# Microcontroller.net
KiCad netlist of a schematic drawn in Altium Designer
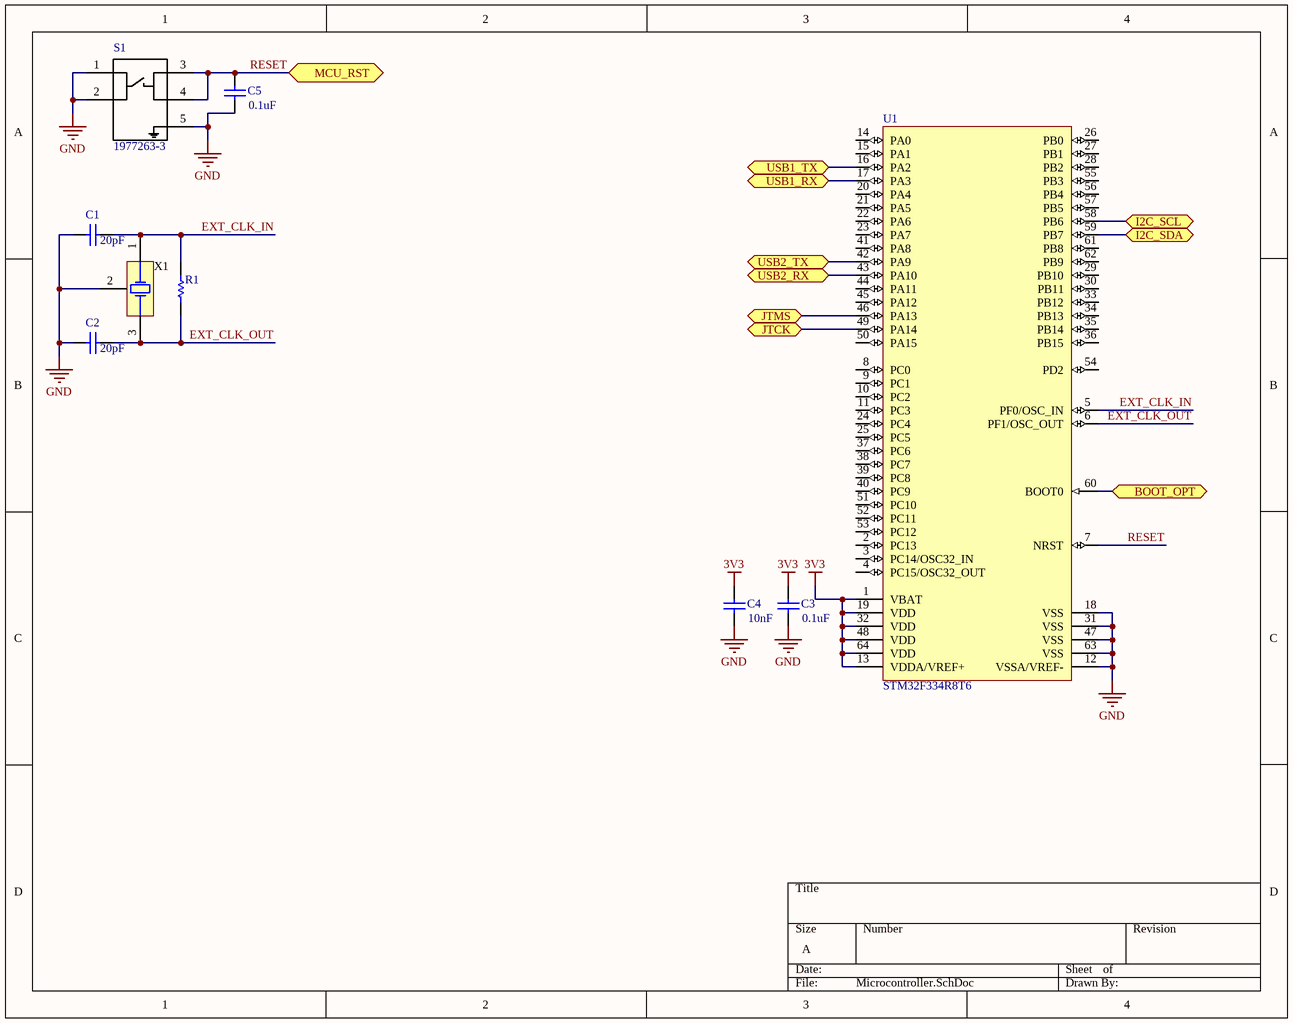
[diagram p0: Microcontroller.SchDoc]

(export (version "E")
  (design (tool "Eeschema 10.0.6"))
  (components
    (comp (ref "C1")
      (value "20pF")
      (footprint "CAPC1206(3216)100_M")
      (description "CAP 20pF 100V ±10% 1206 (3216 Metric) Thickness 1mm SMD")
      (fields (field (name "TOLERANCE") "Â±10%") (field (name "Comment") "CAP 20pF 100V 1206(3216)"))
      (libsource (lib "Altium Content Vault") (part "CAP"))
    )
    (comp (ref "C2")
      (value "20pF")
      (footprint "CAPC1206(3216)100_M")
      (description "CAP 20pF 100V ±10% 1206 (3216 Metric) Thickness 1mm SMD")
      (fields (field (name "TOLERANCE") "Â±10%") (field (name "Comment") "CAP 20pF 100V 1206(3216)"))
      (libsource (lib "Altium Content Vault") (part "CAP"))
    )
    (comp (ref "C3")
      (value "0.1uF")
      (footprint "CAPC3216X100X50LL20T25")
      (description "CAP CER 0.1UF 25V 10% X7R 1206")
      (fields (field (name "PARTNUMBER") "C1206F104K3RACTU"))
      (libsource (lib "Altium Content Vault") (part "CAP-NP-2"))
    )
    (comp (ref "C4")
      (value "C1206C103K1RAC")
      (footprint "CAPC3216X88X50LL20T25")
      (description "Chip Capacitor, 0.01 uF, +/- 10%, 100 V, -55 to 125 degC, 1206 (3216 Metric), RoHS, Tape and Reel")
      (fields (field (name "CAPACITANCE") "10nF") (field (name "MANUFACTURER") "Kemet"))
      (libsource (lib "") (part "CAP-NP-2_1"))
    )
    (comp (ref "C5")
      (value "0.1uF")
      (footprint "CAPC3216X100X50LL20T25")
      (description "CAP CER 0.1UF 25V 10% X7R 1206")
      (fields (field (name "PARTNUMBER") "C1206F104K3RACTU"))
      (libsource (lib "Altium Content Vault") (part "CAP-NP-2"))
    )
    (comp (ref "R1")
      (value "1M8 5% 1206(3216)")
      (footprint "RESC1206(3216)_M")
      (description "1M8 0.25W 5% 1206 (3216 Metric)  SMD")
      (fields (field (name "TOLERANCE") "5 %") (field (name "POWER") "0.25 W"))
      (libsource (lib "Altium Content Vault") (part "RES"))
    )
    (comp (ref "S1")
      (value "1977263-3")
      (footprint "SW_1977263-3")
      (description "Switch Tactile OFF _ON_ SPST Round Button Gull Wing 0.05A 24VDC 1000000Cycle 2.55N SMD Bulk")
      (fields (field (name "MF") "TE Connectivity / AMP"))
      (libsource (lib "HRTAltiumLib") (part "1977263-3"))
    )
    (comp (ref "U1")
      (value "STM32F334R8T6")
      (footprint "STM-LQFP64_L")
      (libsource (lib "Altium Content Vault") (part "MC-ARM-STM32F334-LQFP64"))
    )
    (comp (ref "X1")
      (value "ECS-200-20-4X-3IL")
      (footprint "ECS-4X-3IL")
      (description "Quartz Crystal, 20 MHz, 20 pF, -10 to 70 degC, 2-Pin THD, RoHS, Bulk")
      (fields (field (name "MANUFACTURER") "ECS"))
      (libsource (lib "Altium Content Vault") (part "XTAL-1-3-3"))
    )
  )
  (nets
    (net (code "1") (name "/BOOT_OPT") (class "Default")
      (node (ref "U1") (pin "60") (pinfunction "BOOT0_60") (pintype "input"))
    )
    (net (code "2") (name "/EXT_CLK_IN") (class "Default")
      (node (ref "C1") (pin "2") (pinfunction "2_2") (pintype "passive"))
      (node (ref "R1") (pin "2") (pinfunction "2_2") (pintype "passive"))
      (node (ref "U1") (pin "5") (pinfunction "PF0/OSC_IN_5") (pintype "bidirectional"))
      (node (ref "X1") (pin "1") (pinfunction "1_1") (pintype "passive"))
    )
    (net (code "3") (name "/EXT_CLK_OUT") (class "Default")
      (node (ref "C2") (pin "2") (pinfunction "2_2") (pintype "passive"))
      (node (ref "R1") (pin "1") (pinfunction "1_1") (pintype "passive"))
      (node (ref "U1") (pin "6") (pinfunction "PF1/OSC_OUT_6") (pintype "bidirectional"))
      (node (ref "X1") (pin "3") (pinfunction "3_3") (pintype "passive"))
    )
    (net (code "4") (name "/I2C_SCL") (class "Default")
      (node (ref "U1") (pin "58") (pinfunction "PB6_58") (pintype "bidirectional"))
    )
    (net (code "5") (name "/I2C_SDA") (class "Default")
      (node (ref "U1") (pin "59") (pinfunction "PB7_59") (pintype "bidirectional"))
    )
    (net (code "6") (name "/JTCK") (class "Default")
      (node (ref "U1") (pin "49") (pinfunction "PA14_49") (pintype "bidirectional"))
    )
    (net (code "7") (name "/JTMS") (class "Default")
      (node (ref "U1") (pin "46") (pinfunction "PA13_46") (pintype "bidirectional"))
    )
    (net (code "8") (name "/RESET") (class "Default")
      (node (ref "C5") (pin "1") (pinfunction "1_1") (pintype "passive"))
      (node (ref "S1") (pin "3") (pinfunction "3_3") (pintype "passive"))
      (node (ref "S1") (pin "4") (pinfunction "4_4") (pintype "passive"))
      (node (ref "U1") (pin "7") (pinfunction "NRST_7") (pintype "bidirectional"))
    )
    (net (code "9") (name "/USB1_RX") (class "Default")
      (node (ref "U1") (pin "17") (pinfunction "PA3_17") (pintype "bidirectional"))
    )
    (net (code "10") (name "/USB1_TX") (class "Default")
      (node (ref "U1") (pin "16") (pinfunction "PA2_16") (pintype "bidirectional"))
    )
    (net (code "11") (name "/USB2_RX") (class "Default")
      (node (ref "U1") (pin "43") (pinfunction "PA10_43") (pintype "bidirectional"))
    )
    (net (code "12") (name "/USB2_TX") (class "Default")
      (node (ref "U1") (pin "42") (pinfunction "PA9_42") (pintype "bidirectional"))
    )
    (net (code "13") (name "3V3") (class "Default")
      (node (ref "C3") (pin "1") (pinfunction "1_1") (pintype "passive"))
      (node (ref "C4") (pin "2") (pinfunction "2_2") (pintype "passive"))
      (node (ref "U1") (pin "1") (pinfunction "VBAT_1") (pintype "power_in"))
      (node (ref "U1") (pin "13") (pinfunction "VDDA/VREF+_13") (pintype "power_in"))
      (node (ref "U1") (pin "19") (pinfunction "VDD_19") (pintype "power_in"))
      (node (ref "U1") (pin "32") (pinfunction "VDD_32") (pintype "power_in"))
      (node (ref "U1") (pin "48") (pinfunction "VDD_48") (pintype "power_in"))
      (node (ref "U1") (pin "64") (pinfunction "VDD_64") (pintype "power_in"))
    )
    (net (code "14") (name "GND") (class "Default")
      (node (ref "C1") (pin "1") (pinfunction "1_1") (pintype "passive"))
      (node (ref "C2") (pin "1") (pinfunction "1_1") (pintype "passive"))
      (node (ref "C3") (pin "2") (pinfunction "2_2") (pintype "passive"))
      (node (ref "C4") (pin "1") (pinfunction "1_1") (pintype "passive"))
      (node (ref "C5") (pin "2") (pinfunction "2_2") (pintype "passive"))
      (node (ref "S1") (pin "1") (pinfunction "1_1") (pintype "passive"))
      (node (ref "S1") (pin "2") (pinfunction "2_2") (pintype "passive"))
      (node (ref "S1") (pin "5") (pinfunction "GND_5") (pintype "power_in"))
      (node (ref "U1") (pin "12") (pinfunction "VSSA/VREF-_12") (pintype "power_in"))
      (node (ref "U1") (pin "18") (pinfunction "VSS_18") (pintype "power_in"))
      (node (ref "U1") (pin "31") (pinfunction "VSS_31") (pintype "power_in"))
      (node (ref "U1") (pin "47") (pinfunction "VSS_47") (pintype "power_in"))
      (node (ref "U1") (pin "63") (pinfunction "VSS_63") (pintype "power_in"))
      (node (ref "X1") (pin "2") (pinfunction "2_2") (pintype "passive"))
    )
    (net (code "15") (name "unconnected-(U1-PA0-Pad14)") (class "Default")
      (node (ref "U1") (pin "14") (pinfunction "PA0_14") (pintype "bidirectional"))
    )
    (net (code "16") (name "unconnected-(U1-PA1-Pad15)") (class "Default")
      (node (ref "U1") (pin "15") (pinfunction "PA1_15") (pintype "bidirectional"))
    )
    (net (code "17") (name "unconnected-(U1-PA4-Pad20)") (class "Default")
      (node (ref "U1") (pin "20") (pinfunction "PA4_20") (pintype "bidirectional"))
    )
    (net (code "18") (name "unconnected-(U1-PA5-Pad21)") (class "Default")
      (node (ref "U1") (pin "21") (pinfunction "PA5_21") (pintype "bidirectional"))
    )
    (net (code "19") (name "unconnected-(U1-PA6-Pad22)") (class "Default")
      (node (ref "U1") (pin "22") (pinfunction "PA6_22") (pintype "bidirectional"))
    )
    (net (code "20") (name "unconnected-(U1-PA7-Pad23)") (class "Default")
      (node (ref "U1") (pin "23") (pinfunction "PA7_23") (pintype "bidirectional"))
    )
    (net (code "21") (name "unconnected-(U1-PA8-Pad41)") (class "Default")
      (node (ref "U1") (pin "41") (pinfunction "PA8_41") (pintype "bidirectional"))
    )
    (net (code "22") (name "unconnected-(U1-PA11-Pad44)") (class "Default")
      (node (ref "U1") (pin "44") (pinfunction "PA11_44") (pintype "bidirectional"))
    )
    (net (code "23") (name "unconnected-(U1-PA12-Pad45)") (class "Default")
      (node (ref "U1") (pin "45") (pinfunction "PA12_45") (pintype "bidirectional"))
    )
    (net (code "24") (name "unconnected-(U1-PA15-Pad50)") (class "Default")
      (node (ref "U1") (pin "50") (pinfunction "PA15_50") (pintype "bidirectional"))
    )
    (net (code "25") (name "unconnected-(U1-PB0-Pad26)") (class "Default")
      (node (ref "U1") (pin "26") (pinfunction "PB0_26") (pintype "bidirectional"))
    )
    (net (code "26") (name "unconnected-(U1-PB1-Pad27)") (class "Default")
      (node (ref "U1") (pin "27") (pinfunction "PB1_27") (pintype "bidirectional"))
    )
    (net (code "27") (name "unconnected-(U1-PB2-Pad28)") (class "Default")
      (node (ref "U1") (pin "28") (pinfunction "PB2_28") (pintype "bidirectional"))
    )
    (net (code "28") (name "unconnected-(U1-PB3-Pad55)") (class "Default")
      (node (ref "U1") (pin "55") (pinfunction "PB3_55") (pintype "bidirectional"))
    )
    (net (code "29") (name "unconnected-(U1-PB4-Pad56)") (class "Default")
      (node (ref "U1") (pin "56") (pinfunction "PB4_56") (pintype "bidirectional"))
    )
    (net (code "30") (name "unconnected-(U1-PB5-Pad57)") (class "Default")
      (node (ref "U1") (pin "57") (pinfunction "PB5_57") (pintype "bidirectional"))
    )
    (net (code "31") (name "unconnected-(U1-PB8-Pad61)") (class "Default")
      (node (ref "U1") (pin "61") (pinfunction "PB8_61") (pintype "bidirectional"))
    )
    (net (code "32") (name "unconnected-(U1-PB9-Pad62)") (class "Default")
      (node (ref "U1") (pin "62") (pinfunction "PB9_62") (pintype "bidirectional"))
    )
    (net (code "33") (name "unconnected-(U1-PB10-Pad29)") (class "Default")
      (node (ref "U1") (pin "29") (pinfunction "PB10_29") (pintype "bidirectional"))
    )
    (net (code "34") (name "unconnected-(U1-PB11-Pad30)") (class "Default")
      (node (ref "U1") (pin "30") (pinfunction "PB11_30") (pintype "bidirectional"))
    )
    (net (code "35") (name "unconnected-(U1-PB12-Pad33)") (class "Default")
      (node (ref "U1") (pin "33") (pinfunction "PB12_33") (pintype "bidirectional"))
    )
    (net (code "36") (name "unconnected-(U1-PB13-Pad34)") (class "Default")
      (node (ref "U1") (pin "34") (pinfunction "PB13_34") (pintype "bidirectional"))
    )
    (net (code "37") (name "unconnected-(U1-PB14-Pad35)") (class "Default")
      (node (ref "U1") (pin "35") (pinfunction "PB14_35") (pintype "bidirectional"))
    )
    (net (code "38") (name "unconnected-(U1-PB15-Pad36)") (class "Default")
      (node (ref "U1") (pin "36") (pinfunction "PB15_36") (pintype "bidirectional"))
    )
    (net (code "39") (name "unconnected-(U1-PC0-Pad8)") (class "Default")
      (node (ref "U1") (pin "8") (pinfunction "PC0_8") (pintype "bidirectional"))
    )
    (net (code "40") (name "unconnected-(U1-PC1-Pad9)") (class "Default")
      (node (ref "U1") (pin "9") (pinfunction "PC1_9") (pintype "bidirectional"))
    )
    (net (code "41") (name "unconnected-(U1-PC2-Pad10)") (class "Default")
      (node (ref "U1") (pin "10") (pinfunction "PC2_10") (pintype "bidirectional"))
    )
    (net (code "42") (name "unconnected-(U1-PC3-Pad11)") (class "Default")
      (node (ref "U1") (pin "11") (pinfunction "PC3_11") (pintype "bidirectional"))
    )
    (net (code "43") (name "unconnected-(U1-PC4-Pad24)") (class "Default")
      (node (ref "U1") (pin "24") (pinfunction "PC4_24") (pintype "bidirectional"))
    )
    (net (code "44") (name "unconnected-(U1-PC5-Pad25)") (class "Default")
      (node (ref "U1") (pin "25") (pinfunction "PC5_25") (pintype "bidirectional"))
    )
    (net (code "45") (name "unconnected-(U1-PC6-Pad37)") (class "Default")
      (node (ref "U1") (pin "37") (pinfunction "PC6_37") (pintype "bidirectional"))
    )
    (net (code "46") (name "unconnected-(U1-PC7-Pad38)") (class "Default")
      (node (ref "U1") (pin "38") (pinfunction "PC7_38") (pintype "bidirectional"))
    )
    (net (code "47") (name "unconnected-(U1-PC8-Pad39)") (class "Default")
      (node (ref "U1") (pin "39") (pinfunction "PC8_39") (pintype "bidirectional"))
    )
    (net (code "48") (name "unconnected-(U1-PC9-Pad40)") (class "Default")
      (node (ref "U1") (pin "40") (pinfunction "PC9_40") (pintype "bidirectional"))
    )
    (net (code "49") (name "unconnected-(U1-PC10-Pad51)") (class "Default")
      (node (ref "U1") (pin "51") (pinfunction "PC10_51") (pintype "bidirectional"))
    )
    (net (code "50") (name "unconnected-(U1-PC11-Pad52)") (class "Default")
      (node (ref "U1") (pin "52") (pinfunction "PC11_52") (pintype "bidirectional"))
    )
    (net (code "51") (name "unconnected-(U1-PC12-Pad53)") (class "Default")
      (node (ref "U1") (pin "53") (pinfunction "PC12_53") (pintype "bidirectional"))
    )
    (net (code "52") (name "unconnected-(U1-PC13-Pad2)") (class "Default")
      (node (ref "U1") (pin "2") (pinfunction "PC13_2") (pintype "bidirectional"))
    )
    (net (code "53") (name "unconnected-(U1-PC14{slash}OSC32_IN-Pad3)") (class "Default")
      (node (ref "U1") (pin "3") (pinfunction "PC14/OSC32_IN_3") (pintype "bidirectional"))
    )
    (net (code "54") (name "unconnected-(U1-PC15{slash}OSC32_OUT-Pad4)") (class "Default")
      (node (ref "U1") (pin "4") (pinfunction "PC15/OSC32_OUT_4") (pintype "bidirectional"))
    )
    (net (code "55") (name "unconnected-(U1-PD2-Pad54)") (class "Default")
      (node (ref "U1") (pin "54") (pinfunction "PD2_54") (pintype "bidirectional"))
    )
  )
)
